# STM32F413CG.net
KiCad netlist of a schematic drawn in EAGLE
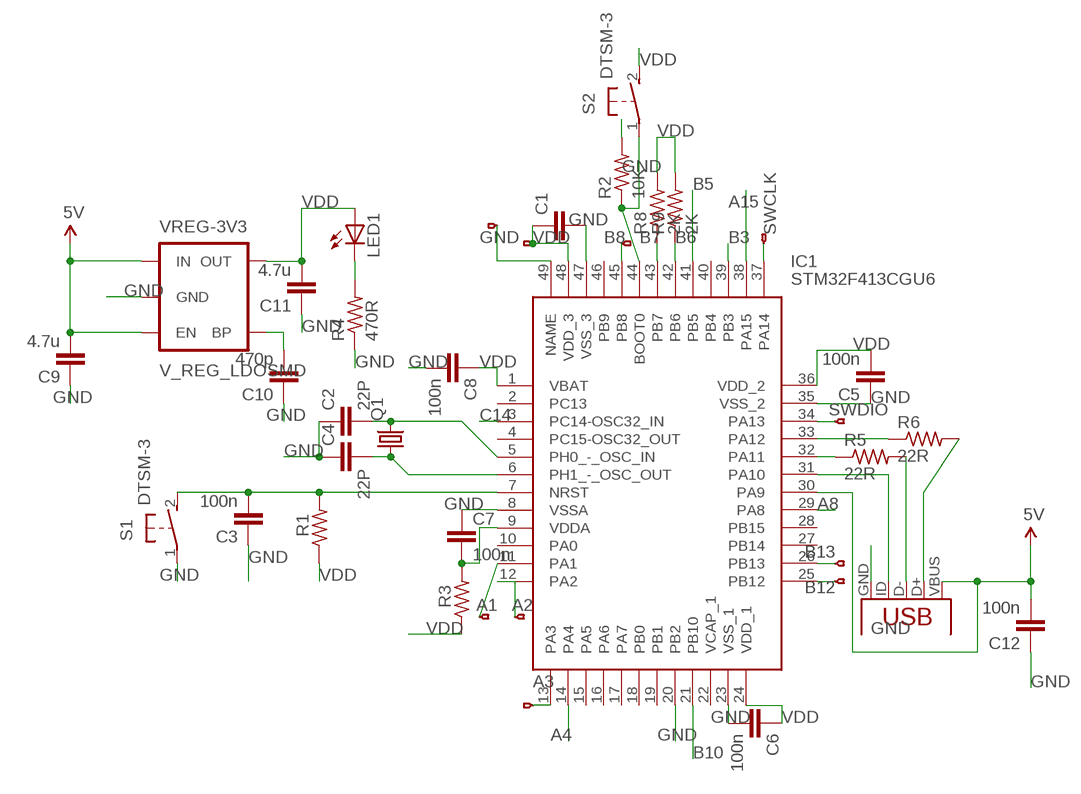
[diagram p0: schematic, sheet 1]
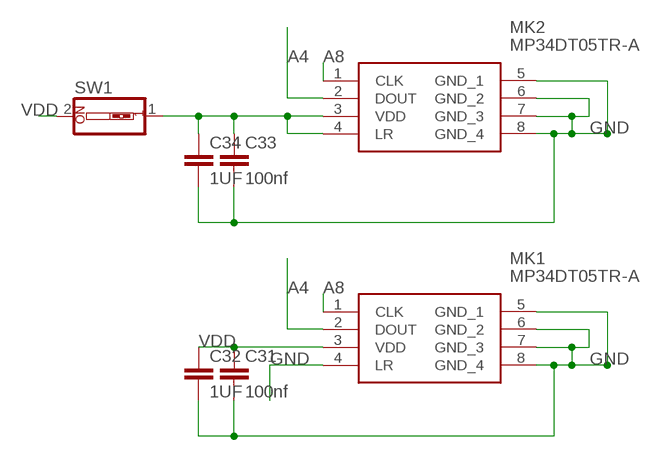
[diagram p1: schematic, sheet 2]
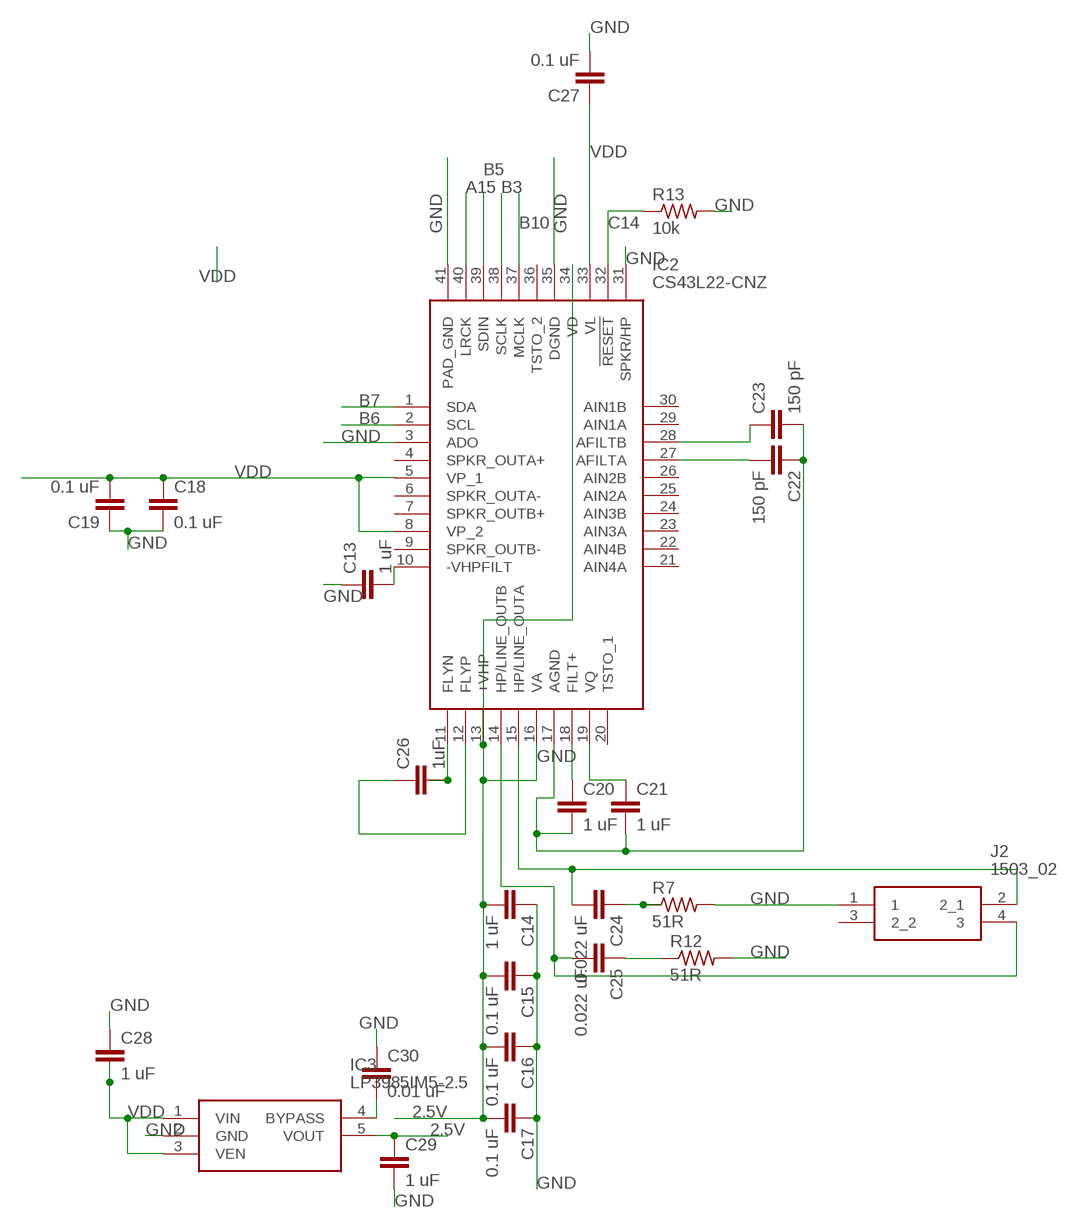
[diagram p2: schematic, sheet 3]

(export (version "E")
  (design (tool "Eeschema 10.0.6"))
  (components
    (comp (ref "C31")
      (value "100nf")
      (footprint "eagle-import:C2.5-2")
      (libsource (lib "eagle-import") (part "C2.5/2"))
    )
    (comp (ref "C32")
      (value "1UF")
      (footprint "eagle-import:C2.5-2")
      (libsource (lib "eagle-import") (part "C2.5/2"))
    )
    (comp (ref "C33")
      (value "100nf")
      (footprint "eagle-import:C2.5-2")
      (libsource (lib "eagle-import") (part "C2.5/2"))
    )
    (comp (ref "C34")
      (value "1UF")
      (footprint "eagle-import:C2.5-2")
      (libsource (lib "eagle-import") (part "C2.5/2"))
    )
    (comp (ref "MK1")
      (value "MP34DT05TR-A")
      (footprint "eagle-import:MP34DT05TRA")
      (fields (field (name "MOUSER_PART_NUMBER") "511-MP34DT05TR-A"))
      (libsource (lib "eagle-import") (part "MP34DT05TR-A"))
    )
    (comp (ref "MK2")
      (value "MP34DT05TR-A")
      (footprint "eagle-import:MP34DT05TRA")
      (fields (field (name "MOUSER_PART_NUMBER") "511-MP34DT05TR-A"))
      (libsource (lib "eagle-import") (part "MP34DT05TR-A"))
    )
    (comp (ref "SW1")
      (value "SW_DIP-1")
      (footprint "eagle-import:EDG-01")
      (libsource (lib "eagle-import") (part "SW_DIP-1"))
    )
    (comp (ref "C13")
      (value "1 uF")
      (footprint "eagle-import:CAP-PTH-SMALL-KIT")
      (libsource (lib "eagle-import") (part "CAPKIT"))
    )
    (comp (ref "C14")
      (value "1 uF")
      (footprint "eagle-import:CAP-PTH-SMALL-KIT")
      (libsource (lib "eagle-import") (part "CAPKIT"))
    )
    (comp (ref "C15")
      (value "0.1 uF")
      (footprint "eagle-import:CAP-PTH-SMALL-KIT")
      (libsource (lib "eagle-import") (part "CAPKIT"))
    )
    (comp (ref "C16")
      (value "0.1 uF")
      (footprint "eagle-import:CAP-PTH-SMALL-KIT")
      (libsource (lib "eagle-import") (part "CAPKIT"))
    )
    (comp (ref "C17")
      (value "0.1 uF")
      (footprint "eagle-import:CAP-PTH-SMALL-KIT")
      (libsource (lib "eagle-import") (part "CAPKIT"))
    )
    (comp (ref "C18")
      (value "0.1 uF")
      (footprint "eagle-import:CAP-PTH-SMALL-KIT")
      (libsource (lib "eagle-import") (part "CAPKIT"))
    )
    (comp (ref "C19")
      (value "0.1 uF")
      (footprint "eagle-import:CAP-PTH-SMALL-KIT")
      (libsource (lib "eagle-import") (part "CAPKIT"))
    )
    (comp (ref "C20")
      (value "1 uF")
      (footprint "eagle-import:CAP-PTH-SMALL-KIT")
      (libsource (lib "eagle-import") (part "CAPKIT"))
    )
    (comp (ref "C21")
      (value "1 uF")
      (footprint "eagle-import:CAP-PTH-SMALL-KIT")
      (libsource (lib "eagle-import") (part "CAPKIT"))
    )
    (comp (ref "C22")
      (value "150 pF")
      (footprint "eagle-import:CAP-PTH-SMALL-KIT")
      (libsource (lib "eagle-import") (part "CAPKIT"))
    )
    (comp (ref "C23")
      (value "150 pF")
      (footprint "eagle-import:CAP-PTH-SMALL-KIT")
      (libsource (lib "eagle-import") (part "CAPKIT"))
    )
    (comp (ref "C24")
      (value "0.022 uF")
      (footprint "eagle-import:CAP-PTH-SMALL-KIT")
      (libsource (lib "eagle-import") (part "CAPKIT"))
    )
    (comp (ref "C25")
      (value "0.022 uF")
      (footprint "eagle-import:CAP-PTH-SMALL-KIT")
      (libsource (lib "eagle-import") (part "CAPKIT"))
    )
    (comp (ref "C26")
      (value "1uF")
      (footprint "eagle-import:C2.5-3")
      (libsource (lib "eagle-import") (part "C2,5-3"))
    )
    (comp (ref "C27")
      (value "0.1 uF")
      (footprint "eagle-import:CAP-PTH-SMALL-KIT")
      (libsource (lib "eagle-import") (part "CAPKIT"))
    )
    (comp (ref "C28")
      (value "1 uF")
      (footprint "eagle-import:CAP-PTH-SMALL-KIT")
      (libsource (lib "eagle-import") (part "CAPKIT"))
    )
    (comp (ref "C29")
      (value "1 uF")
      (footprint "eagle-import:CAP-PTH-SMALL-KIT")
      (libsource (lib "eagle-import") (part "CAPKIT"))
    )
    (comp (ref "C30")
      (value "0.01 uF")
      (footprint "eagle-import:CAP-PTH-SMALL-KIT")
      (libsource (lib "eagle-import") (part "CAPKIT"))
    )
    (comp (ref "IC2")
      (value "CS43L22-CNZ")
      (footprint "eagle-import:QFN50P600X600X100-41N")
      (fields
        (field (name "MOUSER_PART_NUMBER") "777-CS43L22-CNZ")
        (field (name "RS_PART_NUMBER") "7165851P")
      )
      (libsource (lib "eagle-import") (part "CS43L22-CNZ"))
    )
    (comp (ref "IC3")
      (value "LP3985IM5-2.5")
      (footprint "eagle-import:SOT95P300X120-5N")
      (fields
        (field (name "MOUSER_PART_NUMBER") "926-LP3985IM5-25")
        (field (name "RS_PART_NUMBER") "4433167")
      )
      (libsource (lib "eagle-import") (part "LP3985IM5-2.5"))
    )
    (comp (ref "J2")
      (value "1503_02")
      (footprint "eagle-import:150302")
      (fields (field (name "MANUFACTURER_PART_NUMBER") "1503 02"))
      (libsource (lib "eagle-import") (part "1503_02"))
    )
    (comp (ref "R7")
      (value "51R")
      (footprint "eagle-import:0204V")
      (libsource (lib "eagle-import") (part "R-US_0204/2V"))
    )
    (comp (ref "R12")
      (value "51R")
      (footprint "eagle-import:0204V")
      (libsource (lib "eagle-import") (part "R-US_0204/2V"))
    )
    (comp (ref "R13")
      (value "10k")
      (footprint "eagle-import:0204V")
      (libsource (lib "eagle-import") (part "R-US_0204/2V"))
    )
    (comp (ref "C1")
      (value "C2,5-3")
      (footprint "eagle-import:C2.5-3")
      (libsource (lib "eagle-import") (part "C2,5-3"))
    )
    (comp (ref "C2")
      (value "22P")
      (footprint "eagle-import:C2.5-3")
      (libsource (lib "eagle-import") (part "C2,5-3"))
    )
    (comp (ref "C3")
      (value "100n")
      (footprint "eagle-import:C2.5-3")
      (libsource (lib "eagle-import") (part "C2,5-3"))
    )
    (comp (ref "C4")
      (value "22P")
      (footprint "eagle-import:C2.5-3")
      (libsource (lib "eagle-import") (part "C2,5-3"))
    )
    (comp (ref "C5")
      (value "100n")
      (footprint "eagle-import:C2.5-3")
      (libsource (lib "eagle-import") (part "C2,5-3"))
    )
    (comp (ref "C6")
      (value "100n")
      (footprint "eagle-import:C2.5-3")
      (libsource (lib "eagle-import") (part "C2,5-3"))
    )
    (comp (ref "C7")
      (value "100n")
      (footprint "eagle-import:C2.5-3")
      (libsource (lib "eagle-import") (part "C2,5-3"))
    )
    (comp (ref "C8")
      (value "100n")
      (footprint "eagle-import:C2.5-3")
      (libsource (lib "eagle-import") (part "C2,5-3"))
    )
    (comp (ref "C9")
      (value "4.7u")
      (footprint "eagle-import:C2.5-3")
      (libsource (lib "eagle-import") (part "C2,5-3"))
    )
    (comp (ref "C10")
      (value "470p")
      (footprint "eagle-import:C2.5-3")
      (libsource (lib "eagle-import") (part "C2,5-3"))
    )
    (comp (ref "C11")
      (value "4.7u")
      (footprint "eagle-import:C2.5-3")
      (libsource (lib "eagle-import") (part "C2,5-3"))
    )
    (comp (ref "C12")
      (value "100n")
      (footprint "eagle-import:C2.5-3")
      (libsource (lib "eagle-import") (part "C2,5-3"))
    )
    (comp (ref "IC1")
      (value "STM32F413CGU6")
      (footprint "eagle-import:QFN50P700X700X60-49N")
      (fields (field (name "MOUSER_PART_NUMBER") "511-STM32F413CGU6"))
      (libsource (lib "eagle-import") (part "STM32F413CGU6"))
    )
    (comp (ref "JP1")
      (value "HEADERHOLE-HEADERHOLE")
      (footprint "eagle-import:1X1-HEADER-HOLE")
      (libsource (lib "eagle-import") (part "HEADERHOLE-HEADERHOLE"))
    )
    (comp (ref "JP2")
      (value "HEADERHOLE-HEADERHOLE")
      (footprint "eagle-import:1X1-HEADER-HOLE")
      (libsource (lib "eagle-import") (part "HEADERHOLE-HEADERHOLE"))
    )
    (comp (ref "JP3")
      (value "HEADERHOLE-HEADERHOLE")
      (footprint "eagle-import:1X1-HEADER-HOLE")
      (libsource (lib "eagle-import") (part "HEADERHOLE-HEADERHOLE"))
    )
    (comp (ref "JP4")
      (value "HEADERHOLE-HEADERHOLE")
      (footprint "eagle-import:1X1-HEADER-HOLE")
      (libsource (lib "eagle-import") (part "HEADERHOLE-HEADERHOLE"))
    )
    (comp (ref "JP5")
      (value "HEADERHOLE-HEADERHOLE")
      (footprint "eagle-import:1X1-HEADER-HOLE")
      (libsource (lib "eagle-import") (part "HEADERHOLE-HEADERHOLE"))
    )
    (comp (ref "JP6")
      (value "HEADERHOLE-HEADERHOLE")
      (footprint "eagle-import:1X1-HEADER-HOLE")
      (libsource (lib "eagle-import") (part "HEADERHOLE-HEADERHOLE"))
    )
    (comp (ref "JP7")
      (value "HEADERHOLE-HEADERHOLE")
      (footprint "eagle-import:1X1-HEADER-HOLE")
      (libsource (lib "eagle-import") (part "HEADERHOLE-HEADERHOLE"))
    )
    (comp (ref "JP8")
      (value "HEADERHOLE-HEADERHOLE")
      (footprint "eagle-import:1X1-HEADER-HOLE")
      (libsource (lib "eagle-import") (part "HEADERHOLE-HEADERHOLE"))
    )
    (comp (ref "JP9")
      (value "HEADERHOLE-HEADERHOLE")
      (footprint "eagle-import:1X1-HEADER-HOLE")
      (libsource (lib "eagle-import") (part "HEADERHOLE-HEADERHOLE"))
    )
    (comp (ref "JP10")
      (value "HEADERHOLE-HEADERHOLE")
      (footprint "eagle-import:1X1-HEADER-HOLE")
      (libsource (lib "eagle-import") (part "HEADERHOLE-HEADERHOLE"))
    )
    (comp (ref "LED1")
      (value "LED0603")
      (footprint "eagle-import:LED-0603")
      (libsource (lib "eagle-import") (part "LED0603"))
    )
    (comp (ref "Q1")
      (value "CRYSTALHC49S")
      (footprint "eagle-import:HC49_S")
      (libsource (lib "eagle-import") (part "CRYSTALHC49S"))
    )
    (comp (ref "R1")
      (value "R-US_0204/2V")
      (footprint "eagle-import:0204V")
      (libsource (lib "eagle-import") (part "R-US_0204/2V"))
    )
    (comp (ref "R2")
      (value "10K")
      (footprint "eagle-import:0204V")
      (libsource (lib "eagle-import") (part "R-US_0204/2V"))
    )
    (comp (ref "R3")
      (value "R-US_0204/2V")
      (footprint "eagle-import:0204V")
      (libsource (lib "eagle-import") (part "R-US_0204/2V"))
    )
    (comp (ref "R4")
      (value "470R")
      (footprint "eagle-import:0204V")
      (libsource (lib "eagle-import") (part "R-US_0204/2V"))
    )
    (comp (ref "R5")
      (value "22R")
      (footprint "eagle-import:0204V")
      (libsource (lib "eagle-import") (part "R-US_0204/2V"))
    )
    (comp (ref "R6")
      (value "22R")
      (footprint "eagle-import:0204V")
      (libsource (lib "eagle-import") (part "R-US_0204/2V"))
    )
    (comp (ref "R8")
      (value "2K")
      (footprint "eagle-import:0204V")
      (libsource (lib "eagle-import") (part "R-US_0204/2V"))
    )
    (comp (ref "R9")
      (value "2K")
      (footprint "eagle-import:0204V")
      (libsource (lib "eagle-import") (part "R-US_0204/2V"))
    )
    (comp (ref "S1")
      (value "DTSM-3")
      (footprint "eagle-import:DTSM-3")
      (libsource (lib "eagle-import") (part "DTSM-3"))
    )
    (comp (ref "S2")
      (value "DTSM-3")
      (footprint "eagle-import:DTSM-3")
      (libsource (lib "eagle-import") (part "DTSM-3"))
    )
    (comp (ref "VREG-3V3")
      (value "V_REG_LDOSMD")
      (footprint "eagle-import:SOT23-5")
      (libsource (lib "eagle-import") (part "V_REG_LDOSMD"))
    )
    (comp (ref "X1")
      (value "USB-MICROB-SMD")
      (footprint "eagle-import:USB-MICROB-SMD")
      (libsource (lib "eagle-import") (part "USB-MICROB-SMD"))
    )
  )
  (nets
    (net (code "1") (name "2.5V") (class "Default")
      (node (ref "C14") (pin "2") (pinfunction "2_2") (pintype "passive"))
      (node (ref "C15") (pin "2") (pinfunction "2_2") (pintype "passive"))
      (node (ref "C16") (pin "2") (pinfunction "2_2") (pintype "passive"))
      (node (ref "C17") (pin "2") (pinfunction "2_2") (pintype "passive"))
      (node (ref "C29") (pin "1") (pinfunction "1_1") (pintype "passive"))
      (node (ref "IC2") (pin "13") (pinfunction "+VHP_13") (pintype "bidirectional"))
      (node (ref "IC2") (pin "16") (pinfunction "VA_16") (pintype "bidirectional"))
      (node (ref "IC2") (pin "34") (pinfunction "VD_34") (pintype "bidirectional"))
      (node (ref "IC3") (pin "5") (pinfunction "VOUT_5") (pintype "bidirectional"))
    )
    (net (code "2") (name "5V") (class "Default")
      (node (ref "C12") (pin "2") (pinfunction "2_2") (pintype "passive"))
      (node (ref "C9") (pin "2") (pinfunction "2_2") (pintype "passive"))
      (node (ref "IC1") (pin "30") (pinfunction "PA9_30") (pintype "bidirectional"))
      (node (ref "VREG-3V3") (pin "1") (pinfunction "IN_1") (pintype "input"))
      (node (ref "VREG-3V3") (pin "3") (pinfunction "EN_3") (pintype "input"))
      (node (ref "X1") (pin "VBUS") (pinfunction "VBUS_VBUS") (pintype "bidirectional"))
    )
    (net (code "3") (name "A1") (class "Default")
      (node (ref "IC1") (pin "11") (pinfunction "PA1_11") (pintype "bidirectional"))
      (node (ref "JP8") (pin "1") (pinfunction "P$1_1") (pintype "bidirectional"))
    )
    (net (code "4") (name "A2") (class "Default")
      (node (ref "IC1") (pin "12") (pinfunction "PA2_12") (pintype "bidirectional"))
      (node (ref "JP9") (pin "1") (pinfunction "P$1_1") (pintype "bidirectional"))
    )
    (net (code "5") (name "A3") (class "Default")
      (node (ref "IC1") (pin "13") (pinfunction "PA3_13") (pintype "bidirectional"))
      (node (ref "JP10") (pin "1") (pinfunction "P$1_1") (pintype "bidirectional"))
    )
    (net (code "6") (name "A4") (class "Default")
      (node (ref "IC1") (pin "14") (pinfunction "PA4_14") (pintype "bidirectional"))
      (node (ref "MK1") (pin "2") (pinfunction "DOUT_2") (pintype "bidirectional"))
      (node (ref "MK2") (pin "2") (pinfunction "DOUT_2") (pintype "bidirectional"))
    )
    (net (code "7") (name "A8") (class "Default")
      (node (ref "IC1") (pin "29") (pinfunction "PA8_29") (pintype "bidirectional"))
      (node (ref "MK1") (pin "1") (pinfunction "CLK_1") (pintype "bidirectional"))
      (node (ref "MK2") (pin "1") (pinfunction "CLK_1") (pintype "bidirectional"))
    )
    (net (code "8") (name "A15") (class "Default")
      (node (ref "IC1") (pin "38") (pinfunction "PA15_38") (pintype "bidirectional"))
      (node (ref "IC2") (pin "40") (pinfunction "LRCK_40") (pintype "bidirectional"))
    )
    (net (code "9") (name "B3") (class "Default")
      (node (ref "IC1") (pin "39") (pinfunction "PB3_39") (pintype "bidirectional"))
      (node (ref "IC2") (pin "38") (pinfunction "SCLK_38") (pintype "bidirectional"))
    )
    (net (code "10") (name "B5") (class "Default")
      (node (ref "IC1") (pin "41") (pinfunction "PB5_41") (pintype "bidirectional"))
      (node (ref "IC2") (pin "39") (pinfunction "SDIN_39") (pintype "bidirectional"))
    )
    (net (code "11") (name "B6") (class "Default")
      (node (ref "IC1") (pin "42") (pinfunction "PB6_42") (pintype "bidirectional"))
      (node (ref "IC2") (pin "2") (pinfunction "SCL_2") (pintype "bidirectional"))
      (node (ref "R9") (pin "1") (pinfunction "1_1") (pintype "passive"))
    )
    (net (code "12") (name "B7") (class "Default")
      (node (ref "IC1") (pin "43") (pinfunction "PB7_43") (pintype "bidirectional"))
      (node (ref "IC2") (pin "1") (pinfunction "SDA_1") (pintype "bidirectional"))
      (node (ref "R8") (pin "1") (pinfunction "1_1") (pintype "passive"))
    )
    (net (code "13") (name "B8") (class "Default")
      (node (ref "IC1") (pin "45") (pinfunction "PB8_45") (pintype "bidirectional"))
      (node (ref "JP5") (pin "1") (pinfunction "P$1_1") (pintype "bidirectional"))
    )
    (net (code "14") (name "B10") (class "Default")
      (node (ref "IC1") (pin "21") (pinfunction "PB10_21") (pintype "bidirectional"))
      (node (ref "IC2") (pin "37") (pinfunction "MCLK_37") (pintype "bidirectional"))
    )
    (net (code "15") (name "B12") (class "Default")
      (node (ref "IC1") (pin "25") (pinfunction "PB12_25") (pintype "bidirectional"))
      (node (ref "JP7") (pin "1") (pinfunction "P$1_1") (pintype "bidirectional"))
    )
    (net (code "16") (name "B13") (class "Default")
      (node (ref "IC1") (pin "26") (pinfunction "PB13_26") (pintype "bidirectional"))
      (node (ref "JP6") (pin "1") (pinfunction "P$1_1") (pintype "bidirectional"))
    )
    (net (code "17") (name "C14") (class "Default")
      (node (ref "IC1") (pin "3") (pinfunction "PC14-OSC32_IN_3") (pintype "bidirectional"))
      (node (ref "IC2") (pin "32") (pinfunction "~{RESET}_32") (pintype "bidirectional"))
      (node (ref "R13") (pin "1") (pinfunction "1_1") (pintype "passive"))
    )
    (net (code "18") (name "GND") (class "Default")
      (node (ref "C1") (pin "2") (pinfunction "2_2") (pintype "passive"))
      (node (ref "C10") (pin "1") (pinfunction "1_1") (pintype "passive"))
      (node (ref "C11") (pin "1") (pinfunction "1_1") (pintype "passive"))
      (node (ref "C12") (pin "1") (pinfunction "1_1") (pintype "passive"))
      (node (ref "C13") (pin "1") (pinfunction "1_1") (pintype "passive"))
      (node (ref "C14") (pin "1") (pinfunction "1_1") (pintype "passive"))
      (node (ref "C15") (pin "1") (pinfunction "1_1") (pintype "passive"))
      (node (ref "C16") (pin "1") (pinfunction "1_1") (pintype "passive"))
      (node (ref "C17") (pin "1") (pinfunction "1_1") (pintype "passive"))
      (node (ref "C18") (pin "2") (pinfunction "2_2") (pintype "passive"))
      (node (ref "C19") (pin "1") (pinfunction "1_1") (pintype "passive"))
      (node (ref "C2") (pin "1") (pinfunction "1_1") (pintype "passive"))
      (node (ref "C20") (pin "2") (pinfunction "2_2") (pintype "passive"))
      (node (ref "C21") (pin "2") (pinfunction "2_2") (pintype "passive"))
      (node (ref "C22") (pin "1") (pinfunction "1_1") (pintype "passive"))
      (node (ref "C23") (pin "2") (pinfunction "2_2") (pintype "passive"))
      (node (ref "C27") (pin "2") (pinfunction "2_2") (pintype "passive"))
      (node (ref "C28") (pin "1") (pinfunction "1_1") (pintype "passive"))
      (node (ref "C29") (pin "2") (pinfunction "2_2") (pintype "passive"))
      (node (ref "C3") (pin "1") (pinfunction "1_1") (pintype "passive"))
      (node (ref "C30") (pin "1") (pinfunction "1_1") (pintype "passive"))
      (node (ref "C31") (pin "2") (pinfunction "2_2") (pintype "passive"))
      (node (ref "C32") (pin "2") (pinfunction "2_2") (pintype "passive"))
      (node (ref "C33") (pin "2") (pinfunction "2_2") (pintype "passive"))
      (node (ref "C34") (pin "2") (pinfunction "2_2") (pintype "passive"))
      (node (ref "C4") (pin "1") (pinfunction "1_1") (pintype "passive"))
      (node (ref "C5") (pin "1") (pinfunction "1_1") (pintype "passive"))
      (node (ref "C6") (pin "2") (pinfunction "2_2") (pintype "passive"))
      (node (ref "C7") (pin "1") (pinfunction "1_1") (pintype "passive"))
      (node (ref "C8") (pin "2") (pinfunction "2_2") (pintype "passive"))
      (node (ref "C9") (pin "1") (pinfunction "1_1") (pintype "passive"))
      (node (ref "IC1") (pin "20") (pinfunction "PB2_20") (pintype "bidirectional"))
      (node (ref "IC1") (pin "23") (pinfunction "VSS_1_23") (pintype "power_in"))
      (node (ref "IC1") (pin "35") (pinfunction "VSS_2_35") (pintype "power_in"))
      (node (ref "IC1") (pin "47") (pinfunction "VSS_3_47") (pintype "power_in"))
      (node (ref "IC1") (pin "49") (pinfunction "NAME_49") (pintype "bidirectional"))
      (node (ref "IC1") (pin "8") (pinfunction "VSSA_8") (pintype "power_in"))
      (node (ref "IC2") (pin "17") (pinfunction "AGND_17") (pintype "bidirectional"))
      (node (ref "IC2") (pin "3") (pinfunction "ADO_3") (pintype "bidirectional"))
      (node (ref "IC2") (pin "31") (pinfunction "SPKR/HP_31") (pintype "bidirectional"))
      (node (ref "IC2") (pin "35") (pinfunction "DGND_35") (pintype "bidirectional"))
      (node (ref "IC2") (pin "41") (pinfunction "PAD_GND_41") (pintype "bidirectional"))
      (node (ref "IC3") (pin "2") (pinfunction "GND_2") (pintype "bidirectional"))
      (node (ref "J2") (pin "1") (pinfunction "1_1") (pintype "bidirectional"))
      (node (ref "JP1") (pin "1") (pinfunction "P$1_1") (pintype "bidirectional"))
      (node (ref "MK1") (pin "4") (pinfunction "LR_4") (pintype "bidirectional"))
      (node (ref "MK1") (pin "5") (pinfunction "GND_1_5") (pintype "bidirectional"))
      (node (ref "MK1") (pin "6") (pinfunction "GND_2_6") (pintype "bidirectional"))
      (node (ref "MK1") (pin "7") (pinfunction "GND_3_7") (pintype "bidirectional"))
      (node (ref "MK1") (pin "8") (pinfunction "GND_4_8") (pintype "bidirectional"))
      (node (ref "MK2") (pin "5") (pinfunction "GND_1_5") (pintype "bidirectional"))
      (node (ref "MK2") (pin "6") (pinfunction "GND_2_6") (pintype "bidirectional"))
      (node (ref "MK2") (pin "7") (pinfunction "GND_3_7") (pintype "bidirectional"))
      (node (ref "MK2") (pin "8") (pinfunction "GND_4_8") (pintype "bidirectional"))
      (node (ref "R12") (pin "2") (pinfunction "2_2") (pintype "passive"))
      (node (ref "R13") (pin "2") (pinfunction "2_2") (pintype "passive"))
      (node (ref "R2") (pin "2") (pinfunction "2_2") (pintype "passive"))
      (node (ref "R4") (pin "1") (pinfunction "1_1") (pintype "passive"))
      (node (ref "R7") (pin "2") (pinfunction "2_2") (pintype "passive"))
      (node (ref "S1") (pin "1") (pinfunction "1_1") (pintype "passive"))
      (node (ref "VREG-3V3") (pin "2") (pinfunction "GND_2") (pintype "input"))
      (node (ref "X1") (pin "GND") (pinfunction "GND_GND") (pintype "bidirectional"))
    )
    (net (code "19") (name "Net-(C24-Pad1)") (class "Default")
      (node (ref "C24") (pin "1") (pinfunction "1_1") (pintype "passive"))
      (node (ref "R7") (pin "1") (pinfunction "1_1") (pintype "passive"))
    )
    (net (code "20") (name "Net-(C25-Pad1)") (class "Default")
      (node (ref "C25") (pin "1") (pinfunction "1_1") (pintype "passive"))
      (node (ref "R12") (pin "1") (pinfunction "1_1") (pintype "passive"))
    )
    (net (code "21") (name "Net-(IC1-BOOT0)") (class "Default")
      (node (ref "IC1") (pin "44") (pinfunction "BOOT0_44") (pintype "bidirectional"))
      (node (ref "R2") (pin "1") (pinfunction "1_1") (pintype "passive"))
      (node (ref "S2") (pin "1") (pinfunction "1_1") (pintype "passive"))
    )
    (net (code "22") (name "Net-(IC1-NRST)") (class "Default")
      (node (ref "C3") (pin "2") (pinfunction "2_2") (pintype "passive"))
      (node (ref "IC1") (pin "7") (pinfunction "NRST_7") (pintype "bidirectional"))
      (node (ref "R1") (pin "2") (pinfunction "2_2") (pintype "passive"))
      (node (ref "S1") (pin "2") (pinfunction "2_2") (pintype "passive"))
    )
    (net (code "23") (name "Net-(IC1-PA10)") (class "Default")
      (node (ref "IC1") (pin "31") (pinfunction "PA10_31") (pintype "bidirectional"))
      (node (ref "X1") (pin "ID") (pinfunction "ID_ID") (pintype "bidirectional"))
    )
    (net (code "24") (name "Net-(IC1-PA11)") (class "Default")
      (node (ref "IC1") (pin "32") (pinfunction "PA11_32") (pintype "bidirectional"))
      (node (ref "R5") (pin "1") (pinfunction "1_1") (pintype "passive"))
    )
    (net (code "25") (name "Net-(IC1-PA12)") (class "Default")
      (node (ref "IC1") (pin "33") (pinfunction "PA12_33") (pintype "bidirectional"))
      (node (ref "R6") (pin "1") (pinfunction "1_1") (pintype "passive"))
    )
    (net (code "26") (name "Net-(IC1-PH0_-_OSC_IN)") (class "Default")
      (node (ref "C2") (pin "2") (pinfunction "2_2") (pintype "passive"))
      (node (ref "IC1") (pin "5") (pinfunction "PH0_-_OSC_IN_5") (pintype "bidirectional"))
      (node (ref "Q1") (pin "2") (pinfunction "2_2") (pintype "passive"))
    )
    (net (code "27") (name "Net-(IC1-PH1_-_OSC_OUT)") (class "Default")
      (node (ref "C4") (pin "2") (pinfunction "2_2") (pintype "passive"))
      (node (ref "IC1") (pin "6") (pinfunction "PH1_-_OSC_OUT_6") (pintype "bidirectional"))
      (node (ref "Q1") (pin "1") (pinfunction "1_1") (pintype "passive"))
    )
    (net (code "28") (name "Net-(IC1-VDDA)") (class "Default")
      (node (ref "C7") (pin "2") (pinfunction "2_2") (pintype "passive"))
      (node (ref "IC1") (pin "9") (pinfunction "VDDA_9") (pintype "power_in"))
      (node (ref "R3") (pin "2") (pinfunction "2_2") (pintype "passive"))
    )
    (net (code "29") (name "Net-(IC2--VHPFILT)") (class "Default")
      (node (ref "C13") (pin "2") (pinfunction "2_2") (pintype "passive"))
      (node (ref "IC2") (pin "10") (pinfunction "-VHPFILT_10") (pintype "bidirectional"))
    )
    (net (code "30") (name "Net-(IC2-AFILTA)") (class "Default")
      (node (ref "C22") (pin "2") (pinfunction "2_2") (pintype "passive"))
      (node (ref "IC2") (pin "27") (pinfunction "AFILTA_27") (pintype "bidirectional"))
    )
    (net (code "31") (name "Net-(IC2-AFILTB)") (class "Default")
      (node (ref "C23") (pin "1") (pinfunction "1_1") (pintype "passive"))
      (node (ref "IC2") (pin "28") (pinfunction "AFILTB_28") (pintype "bidirectional"))
    )
    (net (code "32") (name "Net-(IC2-FILT+)") (class "Default")
      (node (ref "C20") (pin "1") (pinfunction "1_1") (pintype "passive"))
      (node (ref "IC2") (pin "18") (pinfunction "FILT+_18") (pintype "bidirectional"))
    )
    (net (code "33") (name "Net-(IC2-FLYN)") (class "Default")
      (node (ref "C26") (pin "2") (pinfunction "2_2") (pintype "passive"))
      (node (ref "IC2") (pin "11") (pinfunction "FLYN_11") (pintype "bidirectional"))
    )
    (net (code "34") (name "Net-(IC2-FLYP)") (class "Default")
      (node (ref "C26") (pin "1") (pinfunction "1_1") (pintype "passive"))
      (node (ref "IC2") (pin "12") (pinfunction "FLYP_12") (pintype "bidirectional"))
    )
    (net (code "35") (name "Net-(IC2-HP{slash}LINE_OUTA)") (class "Default")
      (node (ref "C24") (pin "2") (pinfunction "2_2") (pintype "passive"))
      (node (ref "IC2") (pin "15") (pinfunction "HP/LINE_OUTA_15") (pintype "bidirectional"))
      (node (ref "J2") (pin "2") (pinfunction "2_1_2") (pintype "bidirectional"))
    )
    (net (code "36") (name "Net-(IC2-HP{slash}LINE_OUTB)") (class "Default")
      (node (ref "C25") (pin "2") (pinfunction "2_2") (pintype "passive"))
      (node (ref "IC2") (pin "14") (pinfunction "HP/LINE_OUTB_14") (pintype "bidirectional"))
      (node (ref "J2") (pin "4") (pinfunction "3_4") (pintype "bidirectional"))
    )
    (net (code "37") (name "Net-(IC2-VQ)") (class "Default")
      (node (ref "C21") (pin "1") (pinfunction "1_1") (pintype "passive"))
      (node (ref "IC2") (pin "19") (pinfunction "VQ_19") (pintype "bidirectional"))
    )
    (net (code "38") (name "Net-(IC3-BYPASS)") (class "Default")
      (node (ref "C30") (pin "2") (pinfunction "2_2") (pintype "passive"))
      (node (ref "IC3") (pin "4") (pinfunction "BYPASS_4") (pintype "bidirectional"))
    )
    (net (code "39") (name "Net-(LED1-PadC)") (class "Default")
      (node (ref "LED1") (pin "C") (pinfunction "C_C") (pintype "passive"))
      (node (ref "R4") (pin "2") (pinfunction "2_2") (pintype "passive"))
    )
    (net (code "40") (name "Net-(MK2-LR)") (class "Default")
      (node (ref "C33") (pin "1") (pinfunction "1_1") (pintype "passive"))
      (node (ref "C34") (pin "1") (pinfunction "1_1") (pintype "passive"))
      (node (ref "MK2") (pin "3") (pinfunction "VDD_3") (pintype "bidirectional"))
      (node (ref "MK2") (pin "4") (pinfunction "LR_4") (pintype "bidirectional"))
      (node (ref "SW1") (pin "1") (pinfunction "1_1") (pintype "passive"))
    )
    (net (code "41") (name "Net-(R5-Pad2)") (class "Default")
      (node (ref "R5") (pin "2") (pinfunction "2_2") (pintype "passive"))
      (node (ref "X1") (pin "D-") (pinfunction "D-_D-") (pintype "bidirectional"))
    )
    (net (code "42") (name "Net-(R6-Pad2)") (class "Default")
      (node (ref "R6") (pin "2") (pinfunction "2_2") (pintype "passive"))
      (node (ref "X1") (pin "D+") (pinfunction "D+_D+") (pintype "bidirectional"))
    )
    (net (code "43") (name "Net-(VREG-3V3-BP)") (class "Default")
      (node (ref "C10") (pin "2") (pinfunction "2_2") (pintype "passive"))
      (node (ref "VREG-3V3") (pin "4") (pinfunction "BP_4") (pintype "input"))
    )
    (net (code "44") (name "SWCLK") (class "Default")
      (node (ref "IC1") (pin "37") (pinfunction "PA14_37") (pintype "bidirectional"))
      (node (ref "JP2") (pin "1") (pinfunction "P$1_1") (pintype "bidirectional"))
    )
    (net (code "45") (name "SWDIO") (class "Default")
      (node (ref "IC1") (pin "34") (pinfunction "PA13_34") (pintype "bidirectional"))
      (node (ref "JP3") (pin "1") (pinfunction "P$1_1") (pintype "bidirectional"))
    )
    (net (code "46") (name "VCAP_1") (class "Default")
      (node (ref "IC1") (pin "22") (pinfunction "VCAP_1_22") (pintype "power_in"))
    )
    (net (code "47") (name "VDD") (class "Default")
      (node (ref "C1") (pin "1") (pinfunction "1_1") (pintype "passive"))
      (node (ref "C11") (pin "2") (pinfunction "2_2") (pintype "passive"))
      (node (ref "C18") (pin "1") (pinfunction "1_1") (pintype "passive"))
      (node (ref "C19") (pin "2") (pinfunction "2_2") (pintype "passive"))
      (node (ref "C27") (pin "1") (pinfunction "1_1") (pintype "passive"))
      (node (ref "C28") (pin "2") (pinfunction "2_2") (pintype "passive"))
      (node (ref "C31") (pin "1") (pinfunction "1_1") (pintype "passive"))
      (node (ref "C32") (pin "1") (pinfunction "1_1") (pintype "passive"))
      (node (ref "C5") (pin "2") (pinfunction "2_2") (pintype "passive"))
      (node (ref "C6") (pin "1") (pinfunction "1_1") (pintype "passive"))
      (node (ref "C8") (pin "1") (pinfunction "1_1") (pintype "passive"))
      (node (ref "IC1") (pin "1") (pinfunction "VBAT_1") (pintype "power_in"))
      (node (ref "IC1") (pin "24") (pinfunction "VDD_1_24") (pintype "power_in"))
      (node (ref "IC1") (pin "36") (pinfunction "VDD_2_36") (pintype "power_in"))
      (node (ref "IC1") (pin "48") (pinfunction "VDD_3_48") (pintype "power_in"))
      (node (ref "IC2") (pin "33") (pinfunction "VL_33") (pintype "bidirectional"))
      (node (ref "IC2") (pin "5") (pinfunction "VP_1_5") (pintype "bidirectional"))
      (node (ref "IC2") (pin "8") (pinfunction "VP_2_8") (pintype "bidirectional"))
      (node (ref "IC3") (pin "1") (pinfunction "VIN_1") (pintype "bidirectional"))
      (node (ref "IC3") (pin "3") (pinfunction "VEN_3") (pintype "bidirectional"))
      (node (ref "JP4") (pin "1") (pinfunction "P$1_1") (pintype "bidirectional"))
      (node (ref "LED1") (pin "A") (pinfunction "A_A") (pintype "passive"))
      (node (ref "MK1") (pin "3") (pinfunction "VDD_3") (pintype "bidirectional"))
      (node (ref "R1") (pin "1") (pinfunction "1_1") (pintype "passive"))
      (node (ref "R3") (pin "1") (pinfunction "1_1") (pintype "passive"))
      (node (ref "R8") (pin "2") (pinfunction "2_2") (pintype "passive"))
      (node (ref "R9") (pin "2") (pinfunction "2_2") (pintype "passive"))
      (node (ref "S2") (pin "2") (pinfunction "2_2") (pintype "passive"))
      (node (ref "SW1") (pin "2") (pinfunction "2_2") (pintype "passive"))
      (node (ref "VREG-3V3") (pin "5") (pinfunction "OUT_5") (pintype "passive"))
    )
    (net (code "48") (name "unconnected-(IC1-PA0-Pad10)") (class "Default")
      (node (ref "IC1") (pin "10") (pinfunction "PA0_10") (pintype "bidirectional"))
    )
    (net (code "49") (name "unconnected-(IC1-PA5-Pad15)") (class "Default")
      (node (ref "IC1") (pin "15") (pinfunction "PA5_15") (pintype "bidirectional"))
    )
    (net (code "50") (name "unconnected-(IC1-PA6-Pad16)") (class "Default")
      (node (ref "IC1") (pin "16") (pinfunction "PA6_16") (pintype "bidirectional"))
    )
    (net (code "51") (name "unconnected-(IC1-PA7-Pad17)") (class "Default")
      (node (ref "IC1") (pin "17") (pinfunction "PA7_17") (pintype "bidirectional"))
    )
    (net (code "52") (name "unconnected-(IC1-PB0-Pad18)") (class "Default")
      (node (ref "IC1") (pin "18") (pinfunction "PB0_18") (pintype "bidirectional"))
    )
    (net (code "53") (name "unconnected-(IC1-PB1-Pad19)") (class "Default")
      (node (ref "IC1") (pin "19") (pinfunction "PB1_19") (pintype "bidirectional"))
    )
    (net (code "54") (name "unconnected-(IC1-PB4-Pad40)") (class "Default")
      (node (ref "IC1") (pin "40") (pinfunction "PB4_40") (pintype "bidirectional"))
    )
    (net (code "55") (name "unconnected-(IC1-PB9-Pad46)") (class "Default")
      (node (ref "IC1") (pin "46") (pinfunction "PB9_46") (pintype "bidirectional"))
    )
    (net (code "56") (name "unconnected-(IC1-PB14-Pad27)") (class "Default")
      (node (ref "IC1") (pin "27") (pinfunction "PB14_27") (pintype "bidirectional"))
    )
    (net (code "57") (name "unconnected-(IC1-PB15-Pad28)") (class "Default")
      (node (ref "IC1") (pin "28") (pinfunction "PB15_28") (pintype "bidirectional"))
    )
    (net (code "58") (name "unconnected-(IC1-PC13-Pad2)") (class "Default")
      (node (ref "IC1") (pin "2") (pinfunction "PC13_2") (pintype "bidirectional"))
    )
    (net (code "59") (name "unconnected-(IC1-PC15-OSC32_OUT-Pad4)") (class "Default")
      (node (ref "IC1") (pin "4") (pinfunction "PC15-OSC32_OUT_4") (pintype "bidirectional"))
    )
    (net (code "60") (name "unconnected-(IC2-AIN1A-Pad29)") (class "Default")
      (node (ref "IC2") (pin "29") (pinfunction "AIN1A_29") (pintype "bidirectional"))
    )
    (net (code "61") (name "unconnected-(IC2-AIN1B-Pad30)") (class "Default")
      (node (ref "IC2") (pin "30") (pinfunction "AIN1B_30") (pintype "bidirectional"))
    )
    (net (code "62") (name "unconnected-(IC2-AIN2A-Pad25)") (class "Default")
      (node (ref "IC2") (pin "25") (pinfunction "AIN2A_25") (pintype "bidirectional"))
    )
    (net (code "63") (name "unconnected-(IC2-AIN2B-Pad26)") (class "Default")
      (node (ref "IC2") (pin "26") (pinfunction "AIN2B_26") (pintype "bidirectional"))
    )
    (net (code "64") (name "unconnected-(IC2-AIN3A-Pad23)") (class "Default")
      (node (ref "IC2") (pin "23") (pinfunction "AIN3A_23") (pintype "bidirectional"))
    )
    (net (code "65") (name "unconnected-(IC2-AIN3B-Pad24)") (class "Default")
      (node (ref "IC2") (pin "24") (pinfunction "AIN3B_24") (pintype "bidirectional"))
    )
    (net (code "66") (name "unconnected-(IC2-AIN4A-Pad21)") (class "Default")
      (node (ref "IC2") (pin "21") (pinfunction "AIN4A_21") (pintype "bidirectional"))
    )
    (net (code "67") (name "unconnected-(IC2-AIN4B-Pad22)") (class "Default")
      (node (ref "IC2") (pin "22") (pinfunction "AIN4B_22") (pintype "bidirectional"))
    )
    (net (code "68") (name "unconnected-(IC2-SPKR_OUTA+-Pad4)") (class "Default")
      (node (ref "IC2") (pin "4") (pinfunction "SPKR_OUTA+_4") (pintype "bidirectional"))
    )
    (net (code "69") (name "unconnected-(IC2-SPKR_OUTA--Pad6)") (class "Default")
      (node (ref "IC2") (pin "6") (pinfunction "SPKR_OUTA-_6") (pintype "bidirectional"))
    )
    (net (code "70") (name "unconnected-(IC2-SPKR_OUTB+-Pad7)") (class "Default")
      (node (ref "IC2") (pin "7") (pinfunction "SPKR_OUTB+_7") (pintype "bidirectional"))
    )
    (net (code "71") (name "unconnected-(IC2-SPKR_OUTB--Pad9)") (class "Default")
      (node (ref "IC2") (pin "9") (pinfunction "SPKR_OUTB-_9") (pintype "bidirectional"))
    )
    (net (code "72") (name "unconnected-(IC2-TSTO_1-Pad20)") (class "Default")
      (node (ref "IC2") (pin "20") (pinfunction "TSTO_1_20") (pintype "bidirectional"))
    )
    (net (code "73") (name "unconnected-(IC2-TSTO_2-Pad36)") (class "Default")
      (node (ref "IC2") (pin "36") (pinfunction "TSTO_2_36") (pintype "bidirectional"))
    )
    (net (code "74") (name "unconnected-(J2-2_2-Pad3)") (class "Default")
      (node (ref "J2") (pin "3") (pinfunction "2_2_3") (pintype "bidirectional"))
    )
  )
)
